# ledcircuit.net
KiCad netlist of a schematic drawn in EAGLE
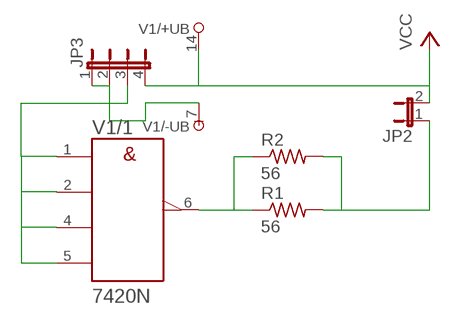
[diagram p0: schematic, sheet 1]

(export (version "E")
  (design (tool "Eeschema 10.0.6"))
  (components
    (comp (ref "JP2")
      (value "JP1E")
      (footprint "eagle-import:JP1")
      (libsource (lib "eagle-import") (part "JP1E"))
    )
    (comp (ref "JP3")
      (value "JP4E")
      (footprint "eagle-import:JP4")
      (libsource (lib "eagle-import") (part "JP4E"))
    )
    (comp (ref "R1")
      (value "56")
      (footprint "eagle-import:0207_10")
      (libsource (lib "eagle-import") (part "R-US_0207/10"))
    )
    (comp (ref "R2")
      (value "56")
      (footprint "eagle-import:0207_10")
      (libsource (lib "eagle-import") (part "R-US_0207/10"))
    )
    (comp (ref "V1")
      (value "7420N")
      (footprint "eagle-import:DIL14")
      (libsource (lib "eagle-import") (part "7420N"))
    )
  )
  (nets
    (net (code "1") (name "Net-(JP2-Pad1)") (class "Default")
      (node (ref "JP2") (pin "1") (pinfunction "1_1") (pintype "passive"))
      (node (ref "R1") (pin "2") (pinfunction "2_2") (pintype "passive"))
      (node (ref "R2") (pin "2") (pinfunction "2_2") (pintype "passive"))
    )
    (net (code "2") (name "Net-(V1B--UB)") (class "Default")
      (node (ref "JP3") (pin "1") (pinfunction "1_1") (pintype "passive"))
      (node (ref "JP3") (pin "2") (pinfunction "2_2") (pintype "passive"))
      (node (ref "V1") (pin "7") (pinfunction "-UB_7") (pintype "power_in"))
    )
    (net (code "3") (name "Net-(V1C-A)") (class "Default")
      (node (ref "JP3") (pin "3") (pinfunction "3_3") (pintype "passive"))
      (node (ref "V1") (pin "1") (pinfunction "A_1") (pintype "input"))
      (node (ref "V1") (pin "2") (pinfunction "B_2") (pintype "input"))
      (node (ref "V1") (pin "4") (pinfunction "C_4") (pintype "input"))
      (node (ref "V1") (pin "5") (pinfunction "D_5") (pintype "input"))
    )
    (net (code "4") (name "Net-(V1C-Y)") (class "Default")
      (node (ref "R1") (pin "1") (pinfunction "1_1") (pintype "passive"))
      (node (ref "R2") (pin "1") (pinfunction "1_1") (pintype "passive"))
      (node (ref "V1") (pin "6") (pinfunction "Y_6") (pintype "output"))
    )
    (net (code "5") (name "VCC") (class "Default")
      (node (ref "JP2") (pin "2") (pinfunction "2_2") (pintype "passive"))
      (node (ref "JP3") (pin "4") (pinfunction "4_4") (pintype "passive"))
      (node (ref "V1") (pin "14") (pinfunction "+UB_14") (pintype "power_in"))
    )
  )
)
